# 05_LMS7002M_RF1.net
KiCad netlist of a schematic drawn in Altium Designer
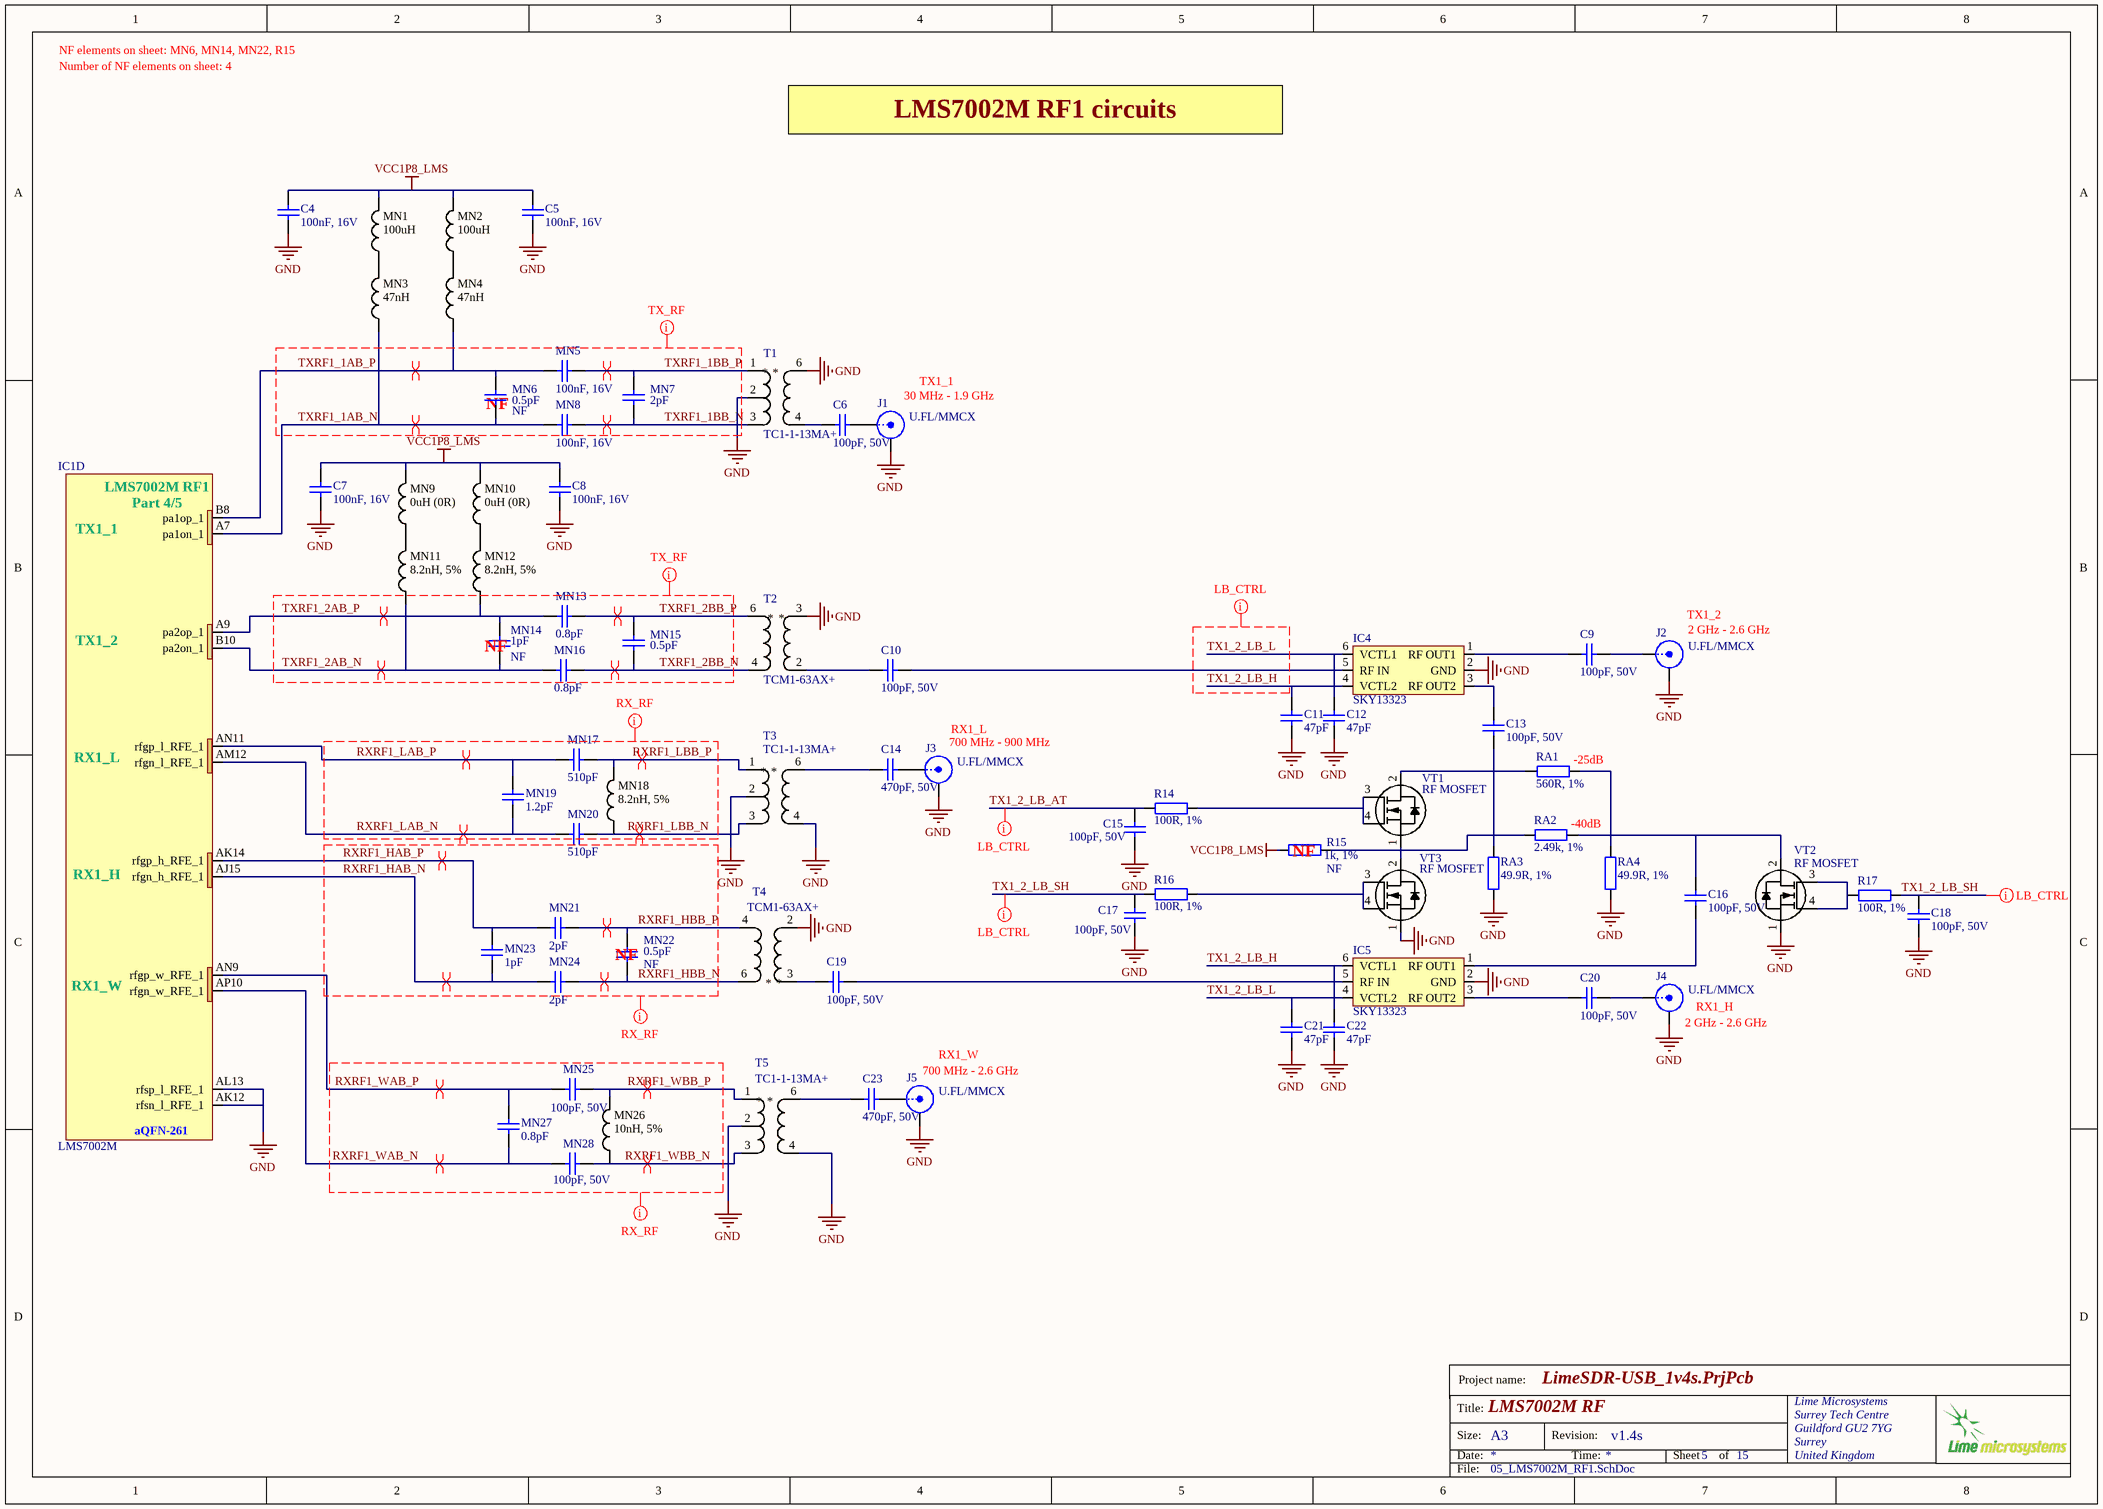
[diagram p0: 05_LMS7002M_RF1.SchDoc]

(export (version "E")
  (design (tool "Eeschema 10.0.6"))
  (components
    (comp (ref "C4")
      (value "100nF, 16V")
      (footprint "CAP0402")
      (fields
        (field (name "MANUFACTURER") "Murata Electronics")
        (field (name "TOLERANCE") "10 %")
        (field (name "MANUFACTURER PART NUMBER") "GRM155R71C104KA88D")
      )
      (libsource (lib "LimeMicroAltiumLib_schLib") (part "Cap_0402"))
    )
    (comp (ref "C5")
      (value "100nF, 16V")
      (footprint "CAP0402")
      (fields
        (field (name "MANUFACTURER") "Murata Electronics")
        (field (name "TOLERANCE") "10 %")
        (field (name "MANUFACTURER PART NUMBER") "GRM155R71C104KA88D")
      )
      (libsource (lib "LimeMicroAltiumLib_schLib") (part "Cap_0402"))
    )
    (comp (ref "C6")
      (value "100pF, 50V")
      (footprint "CAP0402")
      (fields (field (name "TOLERANCE") "±5%") (field (name "MANUFACTURER") "Yageo"))
      (libsource (lib "LimeMicroAltiumLib_schLib") (part "Cap_0402"))
    )
    (comp (ref "C7")
      (value "100nF, 16V")
      (footprint "CAP0402")
      (fields
        (field (name "MANUFACTURER") "Murata Electronics")
        (field (name "TOLERANCE") "10 %")
        (field (name "MANUFACTURER PART NUMBER") "GRM155R71C104KA88D")
      )
      (libsource (lib "LimeMicroAltiumLib_schLib") (part "Cap_0402"))
    )
    (comp (ref "C8")
      (value "100nF, 16V")
      (footprint "CAP0402")
      (fields
        (field (name "MANUFACTURER") "Murata Electronics")
        (field (name "TOLERANCE") "10 %")
        (field (name "MANUFACTURER PART NUMBER") "GRM155R71C104KA88D")
      )
      (libsource (lib "LimeMicroAltiumLib_schLib") (part "Cap_0402"))
    )
    (comp (ref "C9")
      (value "100pF, 50V")
      (footprint "CAP0402")
      (fields (field (name "TOLERANCE") "±5%") (field (name "MANUFACTURER") "Yageo"))
      (libsource (lib "LimeMicroAltiumLib_schLib") (part "Cap_0402"))
    )
    (comp (ref "C10")
      (value "100pF, 50V")
      (footprint "CAP0402")
      (fields (field (name "TOLERANCE") "±5%") (field (name "MANUFACTURER") "Yageo"))
      (libsource (lib "LimeMicroAltiumLib_schLib") (part "Cap_0402"))
    )
    (comp (ref "C11")
      (value "47pF")
      (footprint "CAP0402")
      (fields (field (name "TOLERANCE") "±1%") (field (name "MANUFACTURER") "TDK Corporation"))
      (libsource (lib "LimeMicroAltiumLib_schLib") (part "Cap_0402"))
    )
    (comp (ref "C12")
      (value "47pF")
      (footprint "CAP0402")
      (fields (field (name "TOLERANCE") "±1%") (field (name "MANUFACTURER") "TDK Corporation"))
      (libsource (lib "LimeMicroAltiumLib_schLib") (part "Cap_0402"))
    )
    (comp (ref "C13")
      (value "100pF, 50V")
      (footprint "CAP0402")
      (fields (field (name "TOLERANCE") "±5%") (field (name "MANUFACTURER") "Yageo"))
      (libsource (lib "LimeMicroAltiumLib_schLib") (part "Cap_0402"))
    )
    (comp (ref "C14")
      (value "470pF, 50V")
      (footprint "CAP0402")
      (fields
        (field (name "MANUFACTURER PART NUMBER") "C1005C0G1H471J050BA")
        (field (name "TOLERANCE") "±5%")
        (field (name "MANUFACTURER") "TDK Corporation")
      )
      (libsource (lib "LimeMicroAltiumLib_schLib") (part "Cap_0402"))
    )
    (comp (ref "C15")
      (value "100pF, 50V")
      (footprint "CAP0402")
      (fields (field (name "TOLERANCE") "±5%") (field (name "MANUFACTURER") "Yageo"))
      (libsource (lib "LimeMicroAltiumLib_schLib") (part "Cap_0402"))
    )
    (comp (ref "C16")
      (value "100pF, 50V")
      (footprint "CAP0402")
      (fields (field (name "TOLERANCE") "±5%") (field (name "MANUFACTURER") "Yageo"))
      (libsource (lib "LimeMicroAltiumLib_schLib") (part "Cap_0402"))
    )
    (comp (ref "C17")
      (value "100pF, 50V")
      (footprint "CAP0402")
      (fields (field (name "TOLERANCE") "±5%") (field (name "MANUFACTURER") "Yageo"))
      (libsource (lib "LimeMicroAltiumLib_schLib") (part "Cap_0402"))
    )
    (comp (ref "C18")
      (value "100pF, 50V")
      (footprint "CAP0402")
      (fields (field (name "TOLERANCE") "±5%") (field (name "MANUFACTURER") "Yageo"))
      (libsource (lib "LimeMicroAltiumLib_schLib") (part "Cap_0402"))
    )
    (comp (ref "C19")
      (value "100pF, 50V")
      (footprint "CAP0402")
      (fields (field (name "TOLERANCE") "±5%") (field (name "MANUFACTURER") "Yageo"))
      (libsource (lib "LimeMicroAltiumLib_schLib") (part "Cap_0402"))
    )
    (comp (ref "C20")
      (value "100pF, 50V")
      (footprint "CAP0402")
      (fields (field (name "TOLERANCE") "±5%") (field (name "MANUFACTURER") "Yageo"))
      (libsource (lib "LimeMicroAltiumLib_schLib") (part "Cap_0402"))
    )
    (comp (ref "C21")
      (value "47pF")
      (footprint "CAP0402")
      (fields (field (name "TOLERANCE") "±1%") (field (name "MANUFACTURER") "TDK Corporation"))
      (libsource (lib "LimeMicroAltiumLib_schLib") (part "Cap_0402"))
    )
    (comp (ref "C22")
      (value "47pF")
      (footprint "CAP0402")
      (fields (field (name "TOLERANCE") "±1%") (field (name "MANUFACTURER") "TDK Corporation"))
      (libsource (lib "LimeMicroAltiumLib_schLib") (part "Cap_0402"))
    )
    (comp (ref "C23")
      (value "470pF, 50V")
      (footprint "CAP0402")
      (fields
        (field (name "MANUFACTURER PART NUMBER") "C1005C0G1H471J050BA")
        (field (name "TOLERANCE") "±5%")
        (field (name "MANUFACTURER") "TDK Corporation")
      )
      (libsource (lib "LimeMicroAltiumLib_schLib") (part "Cap_0402"))
    )
    (comp (ref "IC1")
      (value "LMS7002M")
      (footprint "LMS7002M_v3")
      (fields (field (name "MANUFACTURER") "Lime Microsystems"))
      (libsource (lib "LimeMicroAltiumLib_schLib") (part "LMS7002M"))
    )
    (comp (ref "IC4")
      (value "SKY13323")
      (footprint "SKY13323-378LF")
      (description "SKY13323-378LF: 0.1-3.0 GHz GaAs SPDT Switch")
      (fields (field (name "MANUFACTURER") "Skyworks Solutions Inc."))
      (libsource (lib "LimeMicroAltiumLib_schLib") (part "SKY13323"))
    )
    (comp (ref "IC5")
      (value "SKY13323")
      (footprint "SKY13323-378LF")
      (description "SKY13323-378LF: 0.1-3.0 GHz GaAs SPDT Switch")
      (fields (field (name "MANUFACTURER") "Skyworks Solutions Inc."))
      (libsource (lib "LimeMicroAltiumLib_schLib") (part "SKY13323"))
    )
    (comp (ref "J1")
      (value "U.FL/MMCX")
      (footprint "MMCX_UFL_conn_u")
      (description "CONN UMC RCPT STR 50 OHM SMD")
      (fields (field (name "MANUFACTURER") "Molex, LLC"))
      (libsource (lib "LimeMicroAltiumLib_schLib") (part "RF_IF_connector"))
    )
    (comp (ref "J2")
      (value "U.FL/MMCX")
      (footprint "MMCX_UFL_conn_u")
      (description "CONN UMC RCPT STR 50 OHM SMD")
      (fields (field (name "MANUFACTURER") "Molex, LLC"))
      (libsource (lib "LimeMicroAltiumLib_schLib") (part "RF_IF_connector"))
    )
    (comp (ref "J3")
      (value "U.FL/MMCX")
      (footprint "MMCX_UFL_conn_u")
      (description "CONN UMC RCPT STR 50 OHM SMD")
      (fields (field (name "MANUFACTURER") "Molex, LLC"))
      (libsource (lib "LimeMicroAltiumLib_schLib") (part "RF_IF_connector"))
    )
    (comp (ref "J4")
      (value "U.FL/MMCX")
      (footprint "MMCX_UFL_conn_u")
      (description "CONN UMC RCPT STR 50 OHM SMD")
      (fields (field (name "MANUFACTURER") "Molex, LLC"))
      (libsource (lib "LimeMicroAltiumLib_schLib") (part "RF_IF_connector"))
    )
    (comp (ref "J5")
      (value "U.FL/MMCX")
      (footprint "MMCX_UFL_conn_u")
      (description "CONN UMC RCPT STR 50 OHM SMD")
      (fields (field (name "MANUFACTURER") "Molex, LLC"))
      (libsource (lib "LimeMicroAltiumLib_schLib") (part "RF_IF_connector"))
    )
    (comp (ref "MN1")
      (value "100uH")
      (footprint "RES0805")
      (fields
        (field (name "TOLERANCE") "±10%")
        (field (name "MANUFACTURER") "TDK Corporation")
        (field (name "MANUFACTURER PART NUMBER") "MLF2012C101KT000")
      )
      (libsource (lib "LimeMicroAltiumLib_schLib") (part "Inductor_0603"))
    )
    (comp (ref "MN2")
      (value "100uH")
      (footprint "RES0805")
      (fields
        (field (name "TOLERANCE") "±10%")
        (field (name "MANUFACTURER") "TDK Corporation")
        (field (name "MANUFACTURER PART NUMBER") "MLF2012C101KT000")
      )
      (libsource (lib "LimeMicroAltiumLib_schLib") (part "Inductor_0603"))
    )
    (comp (ref "MN3")
      (value "47nH")
      (footprint "RES0402")
      (fields
        (field (name "MANUFACTURER") "COILCRAFT")
        (field (name "MANUFACTURER PART NUMBER") "0402HP-47NXJLU")
      )
      (libsource (lib "LimeMicroAltiumLib_schLib") (part "Inductor_0603"))
    )
    (comp (ref "MN4")
      (value "47nH")
      (footprint "RES0402")
      (fields
        (field (name "MANUFACTURER") "COILCRAFT")
        (field (name "MANUFACTURER PART NUMBER") "0402HP-47NXJLU")
      )
      (libsource (lib "LimeMicroAltiumLib_schLib") (part "Inductor_0603"))
    )
    (comp (ref "MN5")
      (value "100nF, 16V")
      (footprint "CAP0402")
      (fields
        (field (name "MANUFACTURER") "Murata Electronics")
        (field (name "TOLERANCE") "10 %")
        (field (name "MANUFACTURER PART NUMBER") "GRM155R71C104KA88D")
      )
      (libsource (lib "LimeMicroAltiumLib_schLib") (part "Cap_0402"))
    )
    (comp (ref "MN6")
      (value "0.5pF")
      (footprint "CAP0402")
      (fields
        (field (name "ASSEMBLY INFO") "NF")
        (field (name "TOLERANCE") "±0.25pF")
        (field (name "MANUFACTURER") "Yageo")
      )
      (libsource (lib "LimeMicroAltiumLib_schLib") (part "Cap_0402"))
    )
    (comp (ref "MN7")
      (value "2pF")
      (footprint "CAP0402")
      (fields (field (name "MANUFACTURER PART NUMBER") "04025U2R0BAT2A") (field (name "MANUFACTURER") "AVX"))
      (libsource (lib "LimeMicroAltiumLib_schLib") (part "Cap_0402"))
    )
    (comp (ref "MN8")
      (value "100nF, 16V")
      (footprint "CAP0402")
      (fields
        (field (name "MANUFACTURER") "Murata Electronics")
        (field (name "TOLERANCE") "10 %")
        (field (name "MANUFACTURER PART NUMBER") "GRM155R71C104KA88D")
      )
      (libsource (lib "LimeMicroAltiumLib_schLib") (part "Cap_0402"))
    )
    (comp (ref "MN9")
      (value "0uH (0R)")
      (footprint "RES0805")
      (fields (field (name "MANUFACTURER") "BOURNS"))
      (libsource (lib "LimeMicroAltiumLib_schLib") (part "Inductor_0603"))
    )
    (comp (ref "MN10")
      (value "0uH (0R)")
      (footprint "RES0805")
      (fields (field (name "MANUFACTURER") "BOURNS"))
      (libsource (lib "LimeMicroAltiumLib_schLib") (part "Inductor_0603"))
    )
    (comp (ref "MN11")
      (value "8.2nH, 5%")
      (footprint "RES0402")
      (fields (field (name "MANUFACTURER") "COILCRAFT"))
      (libsource (lib "LimeMicroAltiumLib_schLib") (part "Inductor_0603"))
    )
    (comp (ref "MN12")
      (value "8.2nH, 5%")
      (footprint "RES0402")
      (fields (field (name "MANUFACTURER") "COILCRAFT"))
      (libsource (lib "LimeMicroAltiumLib_schLib") (part "Inductor_0603"))
    )
    (comp (ref "MN13")
      (value "0.8pF")
      (footprint "CAP0402")
      (fields
        (field (name "TOLERANCE") "±0.1pF")
        (field (name "MANUFACTURER") "Murata Electronics North America")
        (field (name "MANUFACTURER PART NUMBER") "GRM1555C1HR80BA01D")
      )
      (libsource (lib "LimeMicroAltiumLib_schLib") (part "Cap_0402"))
    )
    (comp (ref "MN14")
      (value "1pF")
      (footprint "CAP0402")
      (fields
        (field (name "ASSEMBLY INFO") "NF")
        (field (name "MANUFACTURER") "TDK Corporation")
        (field (name "TOLERANCE") "±0.1pF")
      )
      (libsource (lib "LimeMicroAltiumLib_schLib") (part "Cap_0402"))
    )
    (comp (ref "MN15")
      (value "0.5pF")
      (footprint "CAP0402")
      (fields (field (name "TOLERANCE") "±0.25pF") (field (name "MANUFACTURER") "Yageo"))
      (libsource (lib "LimeMicroAltiumLib_schLib") (part "Cap_0402"))
    )
    (comp (ref "MN16")
      (value "0.8pF")
      (footprint "CAP0402")
      (fields
        (field (name "TOLERANCE") "±0.1pF")
        (field (name "MANUFACTURER") "Murata Electronics North America")
        (field (name "MANUFACTURER PART NUMBER") "GRM1555C1HR80BA01D")
      )
      (libsource (lib "LimeMicroAltiumLib_schLib") (part "Cap_0402"))
    )
    (comp (ref "MN17")
      (value "510pF")
      (footprint "CAP0402")
      (fields
        (field (name "TOLERANCE") "±5%")
        (field (name "MANUFACTURER") "Murata Electronics North America")
        (field (name "MANUFACTURER PART NUMBER") "GRM1555C1H511JA01D")
      )
      (libsource (lib "LimeMicroAltiumLib_schLib") (part "Cap_0402"))
    )
    (comp (ref "MN18")
      (value "8.2nH, 5%")
      (footprint "RES0402")
      (fields (field (name "MANUFACTURER") "COILCRAFT"))
      (libsource (lib "LimeMicroAltiumLib_schLib") (part "Inductor_0603"))
    )
    (comp (ref "MN19")
      (value "1.2pF")
      (footprint "CAP0402")
      (fields
        (field (name "MANUFACTURER") "Murata Electronics North America")
        (field (name "MANUFACTURER PART NUMBER") "GRM1555C1H1R2CA01D")
        (field (name "TOLERANCE") "±0.25pF")
      )
      (libsource (lib "LimeMicroAltiumLib_schLib") (part "Cap_0402"))
    )
    (comp (ref "MN20")
      (value "510pF")
      (footprint "CAP0402")
      (fields
        (field (name "TOLERANCE") "±5%")
        (field (name "MANUFACTURER") "Murata Electronics North America")
        (field (name "MANUFACTURER PART NUMBER") "GRM1555C1H511JA01D")
      )
      (libsource (lib "LimeMicroAltiumLib_schLib") (part "Cap_0402"))
    )
    (comp (ref "MN21")
      (value "2pF")
      (footprint "CAP0402")
      (fields (field (name "MANUFACTURER PART NUMBER") "04025U2R0BAT2A") (field (name "MANUFACTURER") "AVX"))
      (libsource (lib "LimeMicroAltiumLib_schLib") (part "Cap_0402"))
    )
    (comp (ref "MN22")
      (value "0.5pF")
      (footprint "CAP0402")
      (fields
        (field (name "ASSEMBLY INFO") "NF")
        (field (name "TOLERANCE") "±0.25pF")
        (field (name "MANUFACTURER") "Yageo")
      )
      (libsource (lib "LimeMicroAltiumLib_schLib") (part "Cap_0402"))
    )
    (comp (ref "MN23")
      (value "1pF")
      (footprint "CAP0402")
      (fields (field (name "MANUFACTURER") "TDK Corporation") (field (name "TOLERANCE") "±0.1pF"))
      (libsource (lib "LimeMicroAltiumLib_schLib") (part "Cap_0402"))
    )
    (comp (ref "MN24")
      (value "2pF")
      (footprint "CAP0402")
      (fields (field (name "MANUFACTURER PART NUMBER") "04025U2R0BAT2A") (field (name "MANUFACTURER") "AVX"))
      (libsource (lib "LimeMicroAltiumLib_schLib") (part "Cap_0402"))
    )
    (comp (ref "MN25")
      (value "100pF, 50V")
      (footprint "CAP0402")
      (fields (field (name "TOLERANCE") "±5%") (field (name "MANUFACTURER") "Yageo"))
      (libsource (lib "LimeMicroAltiumLib_schLib") (part "Cap_0402"))
    )
    (comp (ref "MN26")
      (value "10nH, 5%")
      (footprint "RES0402")
      (fields (field (name "MANUFACTURER") "COILCRAFT"))
      (libsource (lib "LimeMicroAltiumLib_schLib") (part "Inductor_0603"))
    )
    (comp (ref "MN27")
      (value "0.8pF")
      (footprint "CAP0402")
      (fields
        (field (name "TOLERANCE") "±0.1pF")
        (field (name "MANUFACTURER") "Murata Electronics North America")
        (field (name "MANUFACTURER PART NUMBER") "GRM1555C1HR80BA01D")
      )
      (libsource (lib "LimeMicroAltiumLib_schLib") (part "Cap_0402"))
    )
    (comp (ref "MN28")
      (value "100pF, 50V")
      (footprint "CAP0402")
      (fields (field (name "TOLERANCE") "±5%") (field (name "MANUFACTURER") "Yageo"))
      (libsource (lib "LimeMicroAltiumLib_schLib") (part "Cap_0402"))
    )
    (comp (ref "R14")
      (value "100R, 1%")
      (footprint "RES0402")
      (fields (field (name "TOLERANCE") "±1%") (field (name "MANUFACTURER") "Stackpole Electronics Inc."))
      (libsource (lib "LimeFPGAboard_schLib") (part "Res_0402"))
    )
    (comp (ref "R15")
      (value "1k, 1%")
      (footprint "RES0402")
      (fields
        (field (name "ASSEMBLY INFO") "NF")
        (field (name "MANUFACTURER") "Stackpole Electronics Inc")
        (field (name "TOLERANCE") "±1%")
      )
      (libsource (lib "LimeMicroAltiumLib_schLib") (part "Res_0402"))
    )
    (comp (ref "R16")
      (value "100R, 1%")
      (footprint "RES0402")
      (fields (field (name "TOLERANCE") "±1%") (field (name "MANUFACTURER") "Stackpole Electronics Inc."))
      (libsource (lib "LimeFPGAboard_schLib") (part "Res_0402"))
    )
    (comp (ref "R17")
      (value "100R, 1%")
      (footprint "RES0402")
      (fields (field (name "TOLERANCE") "±1%") (field (name "MANUFACTURER") "Stackpole Electronics Inc."))
      (libsource (lib "LimeFPGAboard_schLib") (part "Res_0402"))
    )
    (comp (ref "RA1")
      (value "560R, 1%")
      (footprint "RES0402")
      (fields
        (field (name "MANUFACTURER PART NUMBER") "CRCW0402560RFKED")
        (field (name "TOLERANCE") "±1%")
        (field (name "MANUFACTURER") "Vishay Dale")
      )
      (libsource (lib "LimeMicroAltiumLib_schLib") (part "Res_0402"))
    )
    (comp (ref "RA2")
      (value "2.49k, 1%")
      (footprint "RES0402")
      (fields
        (field (name "TOLERANCE") "±1%")
        (field (name "MANUFACTURER PART NUMBER") "RC0402FR-072K49L")
        (field (name "MANUFACTURER") "Yageo")
      )
      (libsource (lib "LimeMicroAltiumLib_schLib") (part "Res_0402"))
    )
    (comp (ref "RA3")
      (value "49.9R, 1%")
      (footprint "RES0402")
      (fields
        (field (name "TOLERANCE") "±1%")
        (field (name "MANUFACTURER") "Samsung Electro-Mechanics America, Inc.")
        (field (name "MANUFACTURER PART NUMBER") "RC1005F49R9CS")
      )
      (libsource (lib "LimeMicroAltiumLib_schLib") (part "Res_0402"))
    )
    (comp (ref "RA4")
      (value "49.9R, 1%")
      (footprint "RES0402")
      (fields
        (field (name "TOLERANCE") "±1%")
        (field (name "MANUFACTURER") "Samsung Electro-Mechanics America, Inc.")
        (field (name "MANUFACTURER PART NUMBER") "RC1005F49R9CS")
      )
      (libsource (lib "LimeMicroAltiumLib_schLib") (part "Res_0402"))
    )
    (comp (ref "T1")
      (value "TC1-1-13MA+")
      (footprint "TC1-1-13MA+_v2")
      (fields (field (name "MANUFACTURER") "Mini-Circuits"))
      (libsource (lib "LimeMicroAltiumLib_schLib") (part "Balun"))
    )
    (comp (ref "T2")
      (value "TCM1-63AX+")
      (footprint "TCM1-63AX+_v2")
      (fields (field (name "MANUFACTURER") "Mini-circuits"))
      (libsource (lib "LimeMicroAltiumLib_schLib") (part "Balun_v2"))
    )
    (comp (ref "T3")
      (value "TC1-1-13MA+")
      (footprint "TC1-1-13MA+_v2")
      (fields (field (name "MANUFACTURER") "Mini-Circuits"))
      (libsource (lib "LimeMicroAltiumLib_schLib") (part "Balun"))
    )
    (comp (ref "T4")
      (value "TCM1-63AX+")
      (footprint "TCM1-63AX+_v2")
      (fields (field (name "MANUFACTURER") "Mini-circuits"))
      (libsource (lib "") (part "Balun_v2_1"))
    )
    (comp (ref "T5")
      (value "TC1-1-13MA+")
      (footprint "TC1-1-13MA+_v2")
      (fields (field (name "MANUFACTURER") "Mini-Circuits"))
      (libsource (lib "LimeMicroAltiumLib_schLib") (part "Balun"))
    )
    (comp (ref "VT1")
      (value "RF MOSFET")
      (footprint "BF1105R_SOT143R4")
      (fields (field (name "MANUFACTURER") "NXP Semiconductors"))
      (libsource (lib "LimeMicroAltiumLib_schLib") (part "BF1105R,215"))
    )
    (comp (ref "VT2")
      (value "RF MOSFET")
      (footprint "BF1105R_SOT143R4")
      (fields (field (name "MANUFACTURER") "NXP Semiconductors"))
      (libsource (lib "LimeMicroAltiumLib_schLib") (part "BF1105R,215"))
    )
    (comp (ref "VT3")
      (value "RF MOSFET")
      (footprint "BF1105R_SOT143R4")
      (fields (field (name "MANUFACTURER") "NXP Semiconductors"))
      (libsource (lib "LimeMicroAltiumLib_schLib") (part "BF1105R,215"))
    )
  )
  (nets
    (net (code "1") (name "/RXRF1_HAB_N") (class "Default")
      (node (ref "IC1") (pin "AJ15") (pinfunction "rfgn_h_RFE_1_AJ15") (pintype "passive"))
      (node (ref "MN23") (pin "1") (pinfunction "1_1") (pintype "passive"))
      (node (ref "MN24") (pin "2") (pinfunction "2_2") (pintype "passive"))
    )
    (net (code "2") (name "/RXRF1_HAB_P") (class "Default")
      (node (ref "IC1") (pin "AK14") (pinfunction "rfgp_h_RFE_1_AK14") (pintype "passive"))
      (node (ref "MN21") (pin "2") (pinfunction "2_2") (pintype "passive"))
      (node (ref "MN23") (pin "2") (pinfunction "2_2") (pintype "passive"))
    )
    (net (code "3") (name "/RXRF1_HBB_N") (class "Default")
      (node (ref "MN22") (pin "1") (pinfunction "1_1") (pintype "passive"))
      (node (ref "MN24") (pin "1") (pinfunction "1_1") (pintype "passive"))
      (node (ref "T4") (pin "6") (pinfunction "6_6") (pintype "passive"))
    )
    (net (code "4") (name "/RXRF1_HBB_P") (class "Default")
      (node (ref "MN21") (pin "1") (pinfunction "1_1") (pintype "passive"))
      (node (ref "MN22") (pin "2") (pinfunction "2_2") (pintype "passive"))
      (node (ref "T4") (pin "4") (pinfunction "4_4") (pintype "passive"))
    )
    (net (code "5") (name "/RXRF1_LAB_N") (class "Default")
      (node (ref "IC1") (pin "AM12") (pinfunction "rfgn_l_RFE_1_AM12") (pintype "passive"))
      (node (ref "MN19") (pin "1") (pinfunction "1_1") (pintype "passive"))
      (node (ref "MN20") (pin "2") (pinfunction "2_2") (pintype "passive"))
    )
    (net (code "6") (name "/RXRF1_LAB_P") (class "Default")
      (node (ref "IC1") (pin "AN11") (pinfunction "rfgp_l_RFE_1_AN11") (pintype "passive"))
      (node (ref "MN17") (pin "2") (pinfunction "2_2") (pintype "passive"))
      (node (ref "MN19") (pin "2") (pinfunction "2_2") (pintype "passive"))
    )
    (net (code "7") (name "/RXRF1_LBB_N") (class "Default")
      (node (ref "MN18") (pin "1") (pinfunction "1_1") (pintype "passive"))
      (node (ref "MN20") (pin "1") (pinfunction "1_1") (pintype "passive"))
      (node (ref "T3") (pin "3") (pinfunction "3_3") (pintype "passive"))
    )
    (net (code "8") (name "/RXRF1_LBB_P") (class "Default")
      (node (ref "MN17") (pin "1") (pinfunction "1_1") (pintype "passive"))
      (node (ref "MN18") (pin "2") (pinfunction "2_2") (pintype "passive"))
      (node (ref "T3") (pin "1") (pinfunction "1_1") (pintype "passive"))
    )
    (net (code "9") (name "/RXRF1_WAB_N") (class "Default")
      (node (ref "IC1") (pin "AP10") (pinfunction "rfgn_w_RFE_1_AP10") (pintype "passive"))
      (node (ref "MN27") (pin "2") (pinfunction "2_2") (pintype "passive"))
      (node (ref "MN28") (pin "2") (pinfunction "2_2") (pintype "passive"))
    )
    (net (code "10") (name "/RXRF1_WAB_P") (class "Default")
      (node (ref "IC1") (pin "AN9") (pinfunction "rfgp_w_RFE_1_AN9") (pintype "passive"))
      (node (ref "MN25") (pin "2") (pinfunction "2_2") (pintype "passive"))
      (node (ref "MN27") (pin "1") (pinfunction "1_1") (pintype "passive"))
    )
    (net (code "11") (name "/RXRF1_WBB_N") (class "Default")
      (node (ref "MN26") (pin "1") (pinfunction "1_1") (pintype "passive"))
      (node (ref "MN28") (pin "1") (pinfunction "1_1") (pintype "passive"))
      (node (ref "T5") (pin "3") (pinfunction "3_3") (pintype "passive"))
    )
    (net (code "12") (name "/RXRF1_WBB_P") (class "Default")
      (node (ref "MN25") (pin "1") (pinfunction "1_1") (pintype "passive"))
      (node (ref "MN26") (pin "2") (pinfunction "2_2") (pintype "passive"))
      (node (ref "T5") (pin "1") (pinfunction "1_1") (pintype "passive"))
    )
    (net (code "13") (name "/TX1_2_LB_AT") (class "Default")
      (node (ref "C15") (pin "1") (pinfunction "1_1") (pintype "passive"))
      (node (ref "R14") (pin "2") (pinfunction "2_2") (pintype "passive"))
    )
    (net (code "14") (name "/TX1_2_LB_H") (class "Default")
      (node (ref "C11") (pin "2") (pinfunction "2_2") (pintype "passive"))
      (node (ref "C22") (pin "2") (pinfunction "2_2") (pintype "passive"))
      (node (ref "IC4") (pin "4") (pinfunction "VCTL2_4") (pintype "input"))
      (node (ref "IC5") (pin "6") (pinfunction "VCTL1_6") (pintype "input"))
    )
    (net (code "15") (name "/TX1_2_LB_L") (class "Default")
      (node (ref "C12") (pin "2") (pinfunction "2_2") (pintype "passive"))
      (node (ref "C21") (pin "2") (pinfunction "2_2") (pintype "passive"))
      (node (ref "IC4") (pin "6") (pinfunction "VCTL1_6") (pintype "input"))
      (node (ref "IC5") (pin "4") (pinfunction "VCTL2_4") (pintype "input"))
    )
    (net (code "16") (name "/TX1_2_LB_SH") (class "Default")
      (node (ref "C17") (pin "1") (pinfunction "1_1") (pintype "passive"))
      (node (ref "C18") (pin "1") (pinfunction "1_1") (pintype "passive"))
      (node (ref "R16") (pin "2") (pinfunction "2_2") (pintype "passive"))
      (node (ref "R17") (pin "1") (pinfunction "1_1") (pintype "passive"))
    )
    (net (code "17") (name "/TXRF1_1AB_N") (class "Default")
      (node (ref "IC1") (pin "A7") (pinfunction "pa1on_1_A7") (pintype "passive"))
      (node (ref "MN3") (pin "1") (pinfunction "1_1") (pintype "passive"))
      (node (ref "MN6") (pin "1") (pinfunction "1_1") (pintype "passive"))
      (node (ref "MN8") (pin "1") (pinfunction "1_1") (pintype "passive"))
    )
    (net (code "18") (name "/TXRF1_1AB_P") (class "Default")
      (node (ref "IC1") (pin "B8") (pinfunction "pa1op_1_B8") (pintype "passive"))
      (node (ref "MN4") (pin "1") (pinfunction "1_1") (pintype "passive"))
      (node (ref "MN5") (pin "2") (pinfunction "2_2") (pintype "passive"))
      (node (ref "MN6") (pin "2") (pinfunction "2_2") (pintype "passive"))
    )
    (net (code "19") (name "/TXRF1_1BB_N") (class "Default")
      (node (ref "MN7") (pin "1") (pinfunction "1_1") (pintype "passive"))
      (node (ref "MN8") (pin "2") (pinfunction "2_2") (pintype "passive"))
      (node (ref "T1") (pin "3") (pinfunction "3_3") (pintype "passive"))
    )
    (net (code "20") (name "/TXRF1_1BB_P") (class "Default")
      (node (ref "MN5") (pin "1") (pinfunction "1_1") (pintype "passive"))
      (node (ref "MN7") (pin "2") (pinfunction "2_2") (pintype "passive"))
      (node (ref "T1") (pin "1") (pinfunction "1_1") (pintype "passive"))
    )
    (net (code "21") (name "/TXRF1_2AB_N") (class "Default")
      (node (ref "IC1") (pin "B10") (pinfunction "pa2on_1_B10") (pintype "passive"))
      (node (ref "MN11") (pin "1") (pinfunction "1_1") (pintype "passive"))
      (node (ref "MN14") (pin "2") (pinfunction "2_2") (pintype "passive"))
      (node (ref "MN16") (pin "2") (pinfunction "2_2") (pintype "passive"))
    )
    (net (code "22") (name "/TXRF1_2AB_P") (class "Default")
      (node (ref "IC1") (pin "A9") (pinfunction "pa2op_1_A9") (pintype "passive"))
      (node (ref "MN12") (pin "1") (pinfunction "1_1") (pintype "passive"))
      (node (ref "MN13") (pin "2") (pinfunction "2_2") (pintype "passive"))
      (node (ref "MN14") (pin "1") (pinfunction "1_1") (pintype "passive"))
    )
    (net (code "23") (name "/TXRF1_2BB_N") (class "Default")
      (node (ref "MN15") (pin "1") (pinfunction "1_1") (pintype "passive"))
      (node (ref "MN16") (pin "1") (pinfunction "1_1") (pintype "passive"))
      (node (ref "T2") (pin "4") (pinfunction "4_4") (pintype "passive"))
    )
    (net (code "24") (name "/TXRF1_2BB_P") (class "Default")
      (node (ref "MN13") (pin "1") (pinfunction "1_1") (pintype "passive"))
      (node (ref "MN15") (pin "2") (pinfunction "2_2") (pintype "passive"))
      (node (ref "T2") (pin "6") (pinfunction "6_6") (pintype "passive"))
    )
    (net (code "25") (name "GND") (class "Default")
      (node (ref "C11") (pin "1") (pinfunction "1_1") (pintype "passive"))
      (node (ref "C12") (pin "1") (pinfunction "1_1") (pintype "passive"))
      (node (ref "C15") (pin "2") (pinfunction "2_2") (pintype "passive"))
      (node (ref "C17") (pin "2") (pinfunction "2_2") (pintype "passive"))
      (node (ref "C18") (pin "2") (pinfunction "2_2") (pintype "passive"))
      (node (ref "C21") (pin "1") (pinfunction "1_1") (pintype "passive"))
      (node (ref "C22") (pin "1") (pinfunction "1_1") (pintype "passive"))
      (node (ref "C4") (pin "1") (pinfunction "1_1") (pintype "passive"))
      (node (ref "C5") (pin "1") (pinfunction "1_1") (pintype "passive"))
      (node (ref "C7") (pin "1") (pinfunction "1_1") (pintype "passive"))
      (node (ref "C8") (pin "1") (pinfunction "1_1") (pintype "passive"))
      (node (ref "IC1") (pin "AK12") (pinfunction "rfsn_l_RFE_1_AK12") (pintype "passive"))
      (node (ref "IC1") (pin "AL13") (pinfunction "rfsp_l_RFE_1_AL13") (pintype "passive"))
      (node (ref "IC4") (pin "2") (pinfunction "GND_2") (pintype "passive"))
      (node (ref "IC5") (pin "2") (pinfunction "GND_2") (pintype "passive"))
      (node (ref "J1") (pin "2") (pinfunction "Y_2") (pintype "passive"))
      (node (ref "J2") (pin "2") (pinfunction "Y_2") (pintype "passive"))
      (node (ref "J3") (pin "2") (pinfunction "Y_2") (pintype "passive"))
      (node (ref "J4") (pin "2") (pinfunction "Y_2") (pintype "passive"))
      (node (ref "J5") (pin "2") (pinfunction "Y_2") (pintype "passive"))
      (node (ref "RA3") (pin "1") (pinfunction "1_1") (pintype "passive"))
      (node (ref "RA4") (pin "1") (pinfunction "1_1") (pintype "passive"))
      (node (ref "T1") (pin "2") (pinfunction "2_2") (pintype "passive"))
      (node (ref "T1") (pin "6") (pinfunction "6_6") (pintype "passive"))
      (node (ref "T2") (pin "3") (pinfunction "3_3") (pintype "passive"))
      (node (ref "T3") (pin "2") (pinfunction "2_2") (pintype "passive"))
      (node (ref "T3") (pin "4") (pinfunction "4_4") (pintype "passive"))
      (node (ref "T4") (pin "2") (pinfunction "2_2") (pintype "passive"))
      (node (ref "T5") (pin "2") (pinfunction "2_2") (pintype "passive"))
      (node (ref "T5") (pin "4") (pinfunction "4_4") (pintype "passive"))
      (node (ref "VT2") (pin "1") (pinfunction "S_1") (pintype "passive"))
      (node (ref "VT3") (pin "1") (pinfunction "S_1") (pintype "passive"))
    )
    (net (code "26") (name "Net-(C6-Pad2)") (class "Default")
      (node (ref "C6") (pin "2") (pinfunction "2_2") (pintype "passive"))
      (node (ref "T1") (pin "4") (pinfunction "4_4") (pintype "passive"))
    )
    (net (code "27") (name "Net-(C10-Pad2)") (class "Default")
      (node (ref "C10") (pin "2") (pinfunction "2_2") (pintype "passive"))
      (node (ref "T2") (pin "2") (pinfunction "2_2") (pintype "passive"))
    )
    (net (code "28") (name "Net-(C14-Pad2)") (class "Default")
      (node (ref "C14") (pin "2") (pinfunction "2_2") (pintype "passive"))
      (node (ref "T3") (pin "6") (pinfunction "6_6") (pintype "passive"))
    )
    (net (code "29") (name "Net-(C19-Pad2)") (class "Default")
      (node (ref "C19") (pin "2") (pinfunction "2_2") (pintype "passive"))
      (node (ref "T4") (pin "3") (pinfunction "3_3") (pintype "passive"))
    )
    (net (code "30") (name "Net-(C23-Pad2)") (class "Default")
      (node (ref "C23") (pin "2") (pinfunction "2_2") (pintype "passive"))
      (node (ref "T5") (pin "6") (pinfunction "6_6") (pintype "passive"))
    )
    (net (code "31") (name "Net-(IC4-RF_IN)") (class "Default")
      (node (ref "C10") (pin "1") (pinfunction "1_1") (pintype "passive"))
      (node (ref "IC4") (pin "5") (pinfunction "RF_IN_5") (pintype "input"))
    )
    (net (code "32") (name "Net-(IC4-RF_OUT1)") (class "Default")
      (node (ref "C9") (pin "2") (pinfunction "2_2") (pintype "passive"))
      (node (ref "IC4") (pin "1") (pinfunction "RF_OUT1_1") (pintype "output"))
    )
    (net (code "33") (name "Net-(IC4-RF_OUT2)") (class "Default")
      (node (ref "C13") (pin "1") (pinfunction "1_1") (pintype "passive"))
      (node (ref "IC4") (pin "3") (pinfunction "RF_OUT2_3") (pintype "output"))
    )
    (net (code "34") (name "Net-(IC5-RF_IN)") (class "Default")
      (node (ref "C19") (pin "1") (pinfunction "1_1") (pintype "passive"))
      (node (ref "IC5") (pin "5") (pinfunction "RF_IN_5") (pintype "input"))
    )
    (net (code "35") (name "Net-(IC5-RF_OUT1)") (class "Default")
      (node (ref "C16") (pin "2") (pinfunction "2_2") (pintype "passive"))
      (node (ref "IC5") (pin "1") (pinfunction "RF_OUT1_1") (pintype "output"))
    )
    (net (code "36") (name "Net-(IC5-RF_OUT2)") (class "Default")
      (node (ref "C20") (pin "2") (pinfunction "2_2") (pintype "passive"))
      (node (ref "IC5") (pin "3") (pinfunction "RF_OUT2_3") (pintype "output"))
    )
    (net (code "37") (name "Net-(J1-X)") (class "Default")
      (node (ref "C6") (pin "1") (pinfunction "1_1") (pintype "passive"))
      (node (ref "J1") (pin "1") (pinfunction "X_1") (pintype "passive"))
    )
    (net (code "38") (name "Net-(J2-X)") (class "Default")
      (node (ref "C9") (pin "1") (pinfunction "1_1") (pintype "passive"))
      (node (ref "J2") (pin "1") (pinfunction "X_1") (pintype "passive"))
    )
    (net (code "39") (name "Net-(J3-X)") (class "Default")
      (node (ref "C14") (pin "1") (pinfunction "1_1") (pintype "passive"))
      (node (ref "J3") (pin "1") (pinfunction "X_1") (pintype "passive"))
    )
    (net (code "40") (name "Net-(J4-X)") (class "Default")
      (node (ref "C20") (pin "1") (pinfunction "1_1") (pintype "passive"))
      (node (ref "J4") (pin "1") (pinfunction "X_1") (pintype "passive"))
    )
    (net (code "41") (name "Net-(J5-X)") (class "Default")
      (node (ref "C23") (pin "1") (pinfunction "1_1") (pintype "passive"))
      (node (ref "J5") (pin "1") (pinfunction "X_1") (pintype "passive"))
    )
    (net (code "42") (name "Net-(MN1-Pad1)") (class "Default")
      (node (ref "MN1") (pin "1") (pinfunction "1_1") (pintype "passive"))
      (node (ref "MN3") (pin "2") (pinfunction "2_2") (pintype "passive"))
    )
    (net (code "43") (name "Net-(MN2-Pad1)") (class "Default")
      (node (ref "MN2") (pin "1") (pinfunction "1_1") (pintype "passive"))
      (node (ref "MN4") (pin "2") (pinfunction "2_2") (pintype "passive"))
    )
    (net (code "44") (name "Net-(MN10-Pad1)") (class "Default")
      (node (ref "MN10") (pin "1") (pinfunction "1_1") (pintype "passive"))
      (node (ref "MN12") (pin "2") (pinfunction "2_2") (pintype "passive"))
    )
    (net (code "45") (name "Net-(MN11-Pad2)") (class "Default")
      (node (ref "MN11") (pin "2") (pinfunction "2_2") (pintype "passive"))
      (node (ref "MN9") (pin "1") (pinfunction "1_1") (pintype "passive"))
    )
    (net (code "46") (name "Net-(VT1-D)") (class "Default")
      (node (ref "RA1") (pin "2") (pinfunction "2_2") (pintype "passive"))
      (node (ref "VT1") (pin "2") (pinfunction "D_2") (pintype "passive"))
    )
    (net (code "47") (name "Net-(VT1-G1)") (class "Default")
      (node (ref "R14") (pin "1") (pinfunction "1_1") (pintype "passive"))
      (node (ref "VT1") (pin "3") (pinfunction "G2_3") (pintype "passive"))
      (node (ref "VT1") (pin "4") (pinfunction "G1_4") (pintype "passive"))
    )
    (net (code "48") (name "Net-(VT1-S)") (class "Default")
      (node (ref "C13") (pin "2") (pinfunction "2_2") (pintype "passive"))
      (node (ref "R15") (pin "1") (pinfunction "1_1") (pintype "passive"))
      (node (ref "RA2") (pin "1") (pinfunction "1_1") (pintype "passive"))
      (node (ref "RA3") (pin "2") (pinfunction "2_2") (pintype "passive"))
      (node (ref "VT1") (pin "1") (pinfunction "S_1") (pintype "passive"))
      (node (ref "VT3") (pin "2") (pinfunction "D_2") (pintype "passive"))
    )
    (net (code "49") (name "Net-(VT2-D)") (class "Default")
      (node (ref "C16") (pin "1") (pinfunction "1_1") (pintype "passive"))
      (node (ref "RA1") (pin "1") (pinfunction "1_1") (pintype "passive"))
      (node (ref "RA2") (pin "2") (pinfunction "2_2") (pintype "passive"))
      (node (ref "RA4") (pin "2") (pinfunction "2_2") (pintype "passive"))
      (node (ref "VT2") (pin "2") (pinfunction "D_2") (pintype "passive"))
    )
    (net (code "50") (name "Net-(VT2-G1)") (class "Default")
      (node (ref "R17") (pin "2") (pinfunction "2_2") (pintype "passive"))
      (node (ref "VT2") (pin "3") (pinfunction "G2_3") (pintype "passive"))
      (node (ref "VT2") (pin "4") (pinfunction "G1_4") (pintype "passive"))
    )
    (net (code "51") (name "Net-(VT3-G1)") (class "Default")
      (node (ref "R16") (pin "1") (pinfunction "1_1") (pintype "passive"))
      (node (ref "VT3") (pin "3") (pinfunction "G2_3") (pintype "passive"))
      (node (ref "VT3") (pin "4") (pinfunction "G1_4") (pintype "passive"))
    )
    (net (code "52") (name "VCC1P8_LMS") (class "Default")
      (node (ref "C4") (pin "2") (pinfunction "2_2") (pintype "passive"))
      (node (ref "C5") (pin "2") (pinfunction "2_2") (pintype "passive"))
      (node (ref "C7") (pin "2") (pinfunction "2_2") (pintype "passive"))
      (node (ref "C8") (pin "2") (pinfunction "2_2") (pintype "passive"))
      (node (ref "MN1") (pin "2") (pinfunction "2_2") (pintype "passive"))
      (node (ref "MN10") (pin "2") (pinfunction "2_2") (pintype "passive"))
      (node (ref "MN2") (pin "2") (pinfunction "2_2") (pintype "passive"))
      (node (ref "MN9") (pin "2") (pinfunction "2_2") (pintype "passive"))
      (node (ref "R15") (pin "2") (pinfunction "2_2") (pintype "passive"))
    )
  )
)
